# SCH_Esp-Wled-_ready__2024-12-15.net
KiCad netlist of a schematic drawn in EasyEDA
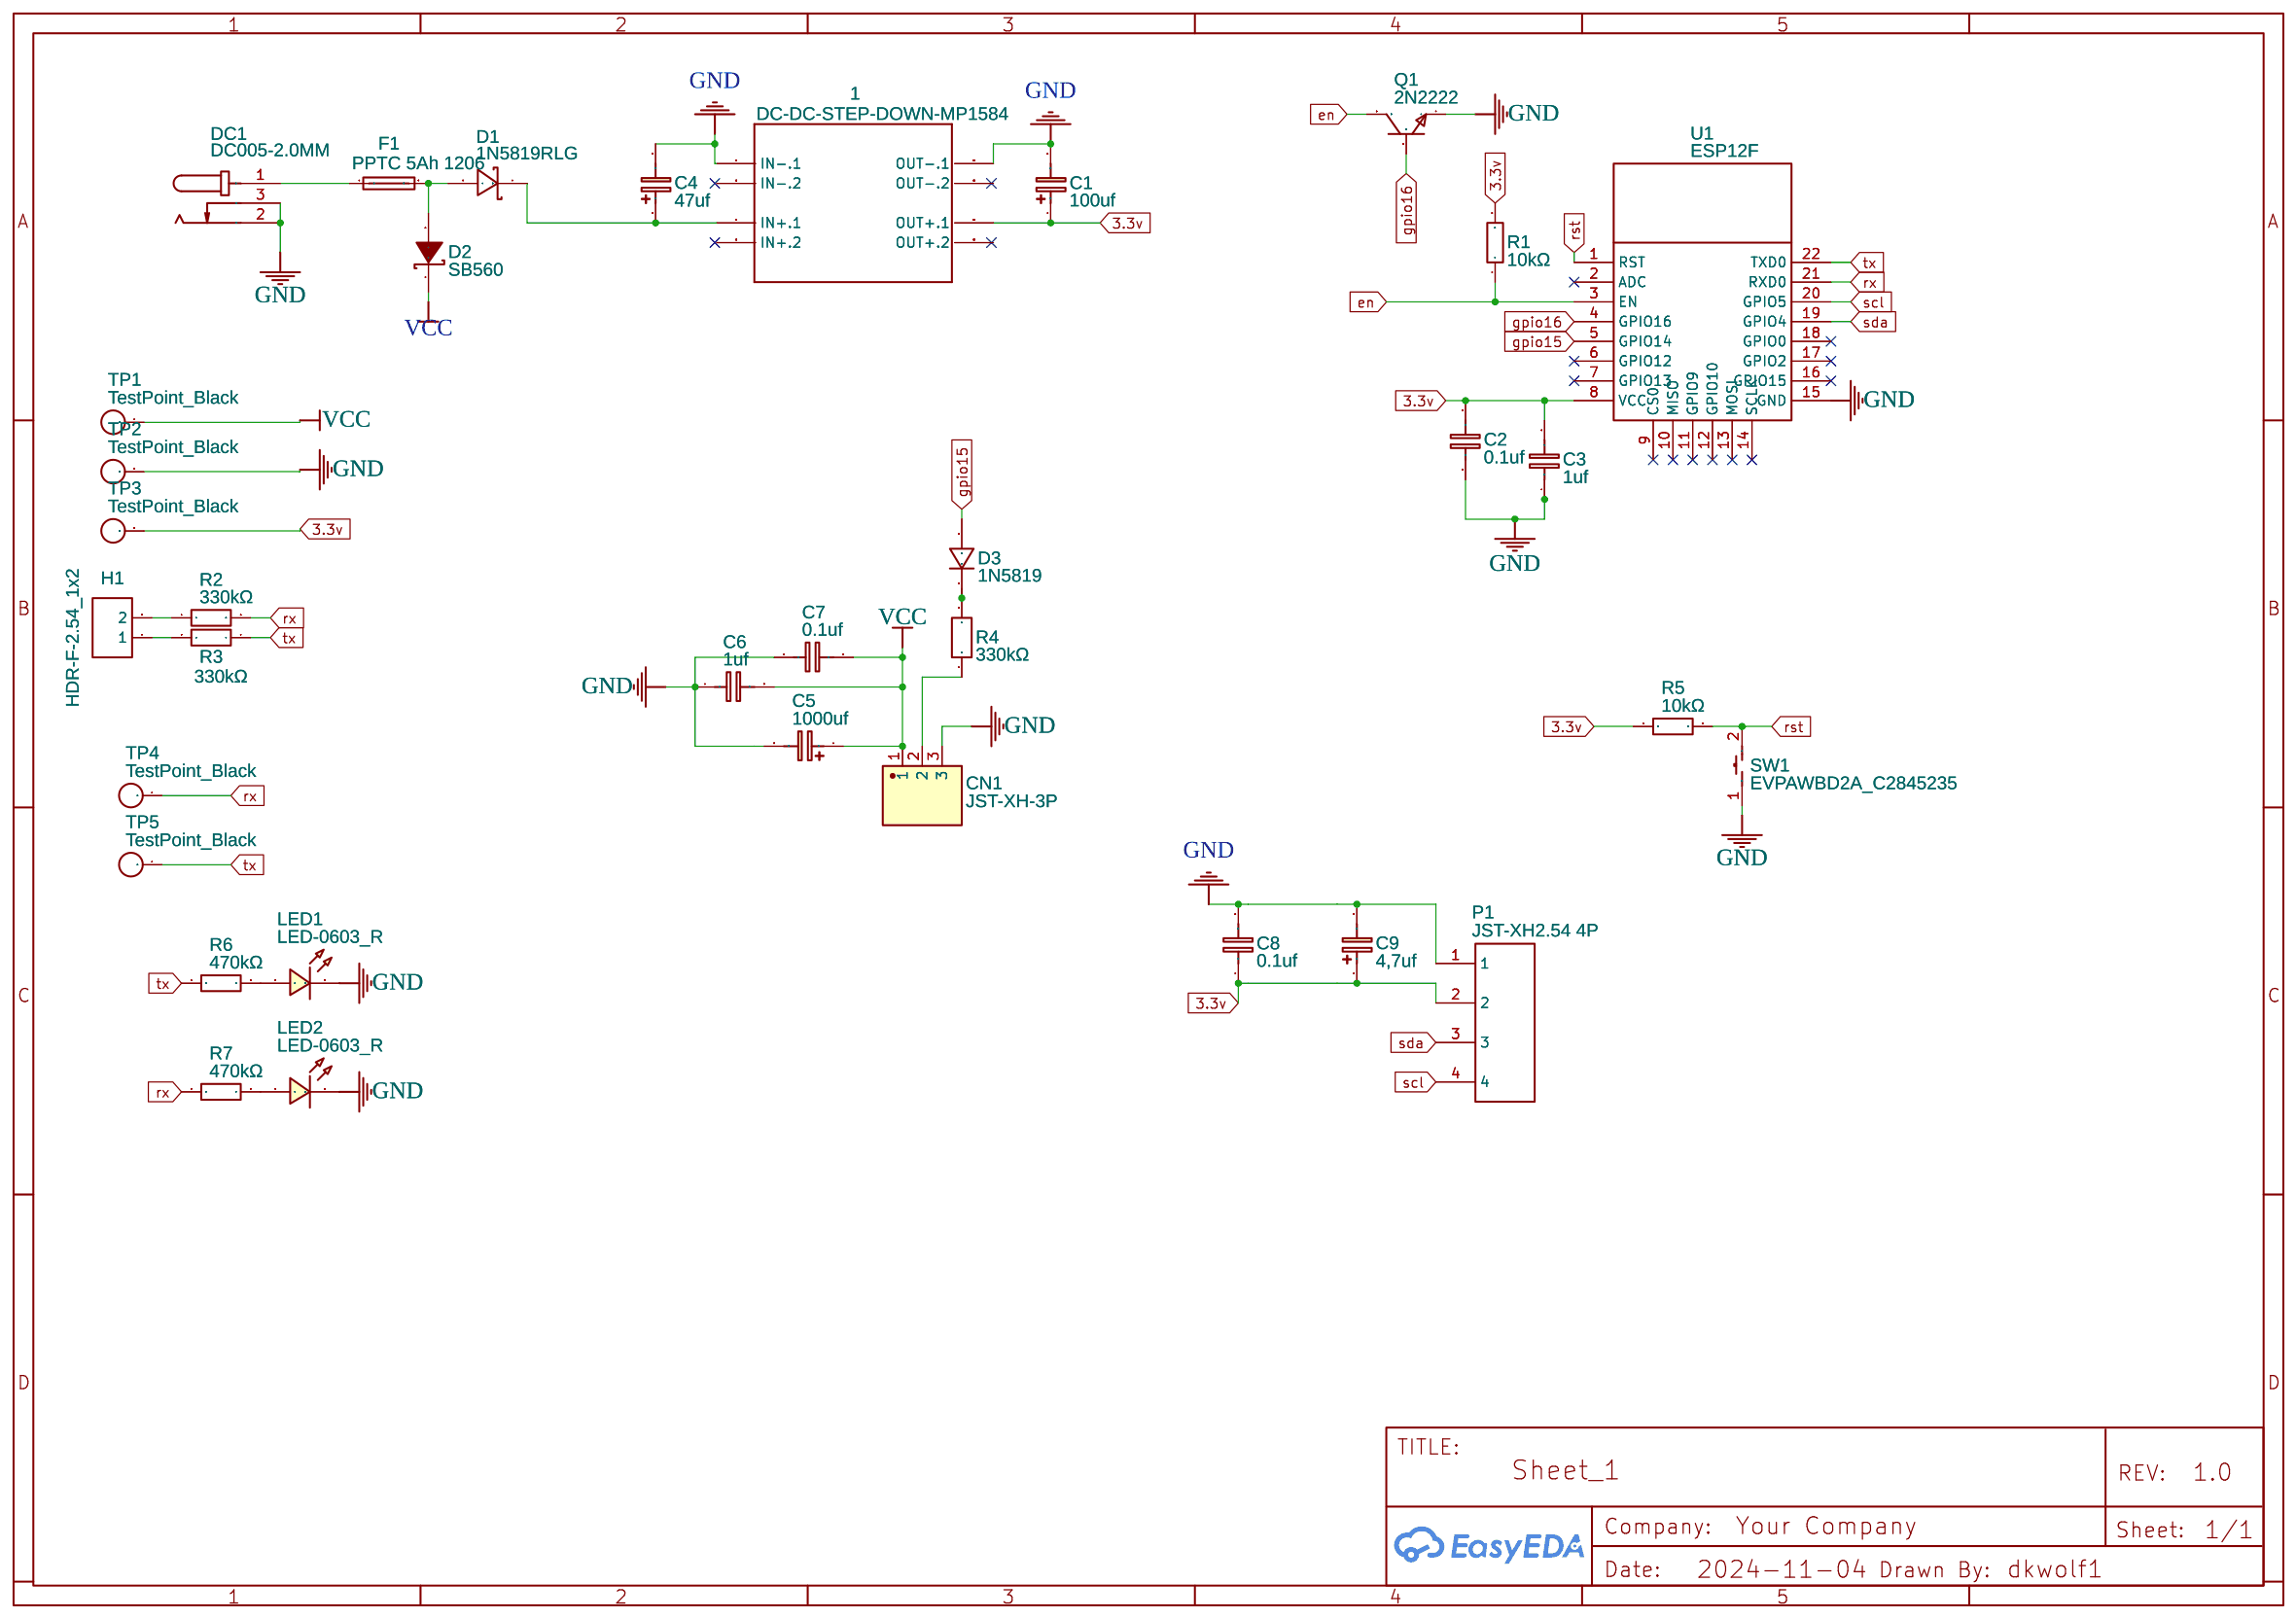
[diagram p0: schematic sheet]

(export (version "E")
  (design (tool "Eeschema 10.0.6"))
  (components
    (comp (ref "1") (value "DC-DC-STEP-DOWN-MP1584") (libsource (lib "") (part "DC-DC-STEP-DOWN-MP1584")))
    (comp (ref "C1") (value "100uf") (libsource (lib "") (part "CE_SMD_D5.0×H5.5_EU_2")))
    (comp (ref "C2") (value "0.1uf") (libsource (lib "") (part "C_0603_EU")))
    (comp (ref "C3") (value "1uf") (libsource (lib "") (part "C_0603_EU")))
    (comp (ref "C4") (value "47uf") (libsource (lib "") (part "CE_SMD_D5.0×H5.5_EU")))
    (comp (ref "C5") (value "1000uf") (libsource (lib "") (part "CE_SMD_D8.0×H10.5_EU")))
    (comp (ref "C6") (value "1uf") (libsource (lib "") (part "C_0603_EU_1")))
    (comp (ref "C7") (value "0.1uf") (libsource (lib "") (part "C_0603_EU_1")))
    (comp (ref "C8") (value "0.1uf") (libsource (lib "") (part "C_0603_EU_2")))
    (comp (ref "C9") (value "4,7uf") (libsource (lib "") (part "CE_SMD_D5.0×H5.5_EU_1")))
    (comp (ref "CN1")
      (value "JST-XH-3P")
      (fields (field (name "Manufacturer Part") "B4B-XH-A(LF)(SN)") (field (name "Manufacturer") "JST"))
      (libsource (lib "") (part "JST-XH-3P"))
    )
    (comp (ref "D1")
      (value "1N5819RLG")
      (fields (field (name "Manufacturer") "onsemi(安森美)"))
      (libsource (lib "") (part "1N5819RLG"))
    )
    (comp (ref "D2")
      (value "SB560")
      (fields (field (name "Manufacturer") "SMC(桑德斯)"))
      (libsource (lib "") (part "SB560"))
    )
    (comp (ref "D3")
      (value "1N5819")
      (fields (field (name "Manufacturer Part") "1N4007") (field (name "Manufacturer") "SEMTECH"))
      (libsource (lib "") (part "1N4007"))
    )
    (comp (ref "DC1")
      (value "DC005-2.0MM")
      (fields (field (name "Manufacturer") "SOFNG"))
      (libsource (lib "") (part "DC005-2.0MM"))
    )
    (comp (ref "F1")
      (value "PPTC 5Ah 1206")
      (fields (field (name "Manufacturer Part") "JK-nSMD050-24") (field (name "Manufacturer") "JK(金科)"))
      (libsource (lib "") (part "JK-NSMD050-24V"))
    )
    (comp (ref "H1") (value "HDR-F-2.54_1x2") (libsource (lib "") (part "HDR-F-2.54_1x2")))
    (comp (ref "LED1")
      (value "LED-0603_R")
      (fields
        (field (name "Manufacturer Part") "19-217/R6C-AL1M2VY/3T")
        (field (name "Manufacturer") "EVERLIGHT(台湾亿光)")
      )
      (libsource (lib "") (part "LED-0603_R"))
    )
    (comp (ref "LED2")
      (value "LED-0603_R")
      (fields
        (field (name "Manufacturer Part") "19-217/R6C-AL1M2VY/3T")
        (field (name "Manufacturer") "EVERLIGHT(台湾亿光)")
      )
      (libsource (lib "") (part "LED-0603_R"))
    )
    (comp (ref "P1") (value "JST-XH2.54 4P") (libsource (lib "") (part "JST-XH2.54 4P")))
    (comp (ref "Q1")
      (value "2N2222")
      (fields (field (name "Manufacturer Part") "2N2222A") (field (name "Manufacturer") "ST(先科)"))
      (libsource (lib "") (part "2N2222"))
    )
    (comp (ref "R1")
      (value "10kΩ")
      (fields (field (name "Manufacturer Part") "RC1206JR-0710KL") (field (name "Manufacturer") "YAGEO(国巨)"))
      (libsource (lib "") (part "RC1206JR-0710KL_1"))
    )
    (comp (ref "R2")
      (value "330kΩ")
      (fields
        (field (name "Manufacturer Part") "1206W4F3303T5E")
        (field (name "Manufacturer") "UNI-ROYAL(厚声)")
      )
      (libsource (lib "") (part "1206W4F3303T5E"))
    )
    (comp (ref "R3")
      (value "330kΩ")
      (fields
        (field (name "Manufacturer Part") "1206W4F3303T5E")
        (field (name "Manufacturer") "UNI-ROYAL(厚声)")
      )
      (libsource (lib "") (part "1206W4F3303T5E_1"))
    )
    (comp (ref "R4")
      (value "330kΩ")
      (fields (field (name "Manufacturer Part") "RC1206JR-7W330KL") (field (name "Manufacturer") "YAGEO(国巨)"))
      (libsource (lib "") (part "RC1206JR-7W330KL"))
    )
    (comp (ref "R5")
      (value "10kΩ")
      (fields (field (name "Manufacturer Part") "RC1206JR-0710KL") (field (name "Manufacturer") "YAGEO(国巨)"))
      (libsource (lib "") (part "RC1206JR-0710KL"))
    )
    (comp (ref "R6")
      (value "470kΩ")
      (fields (field (name "Manufacturer Part") "RC1206FR-07470KL") (field (name "Manufacturer") "YAGEO(国巨)"))
      (libsource (lib "") (part "RC1206FR-07470KL"))
    )
    (comp (ref "R7")
      (value "470kΩ")
      (fields (field (name "Manufacturer Part") "RC1206FR-07470KL") (field (name "Manufacturer") "YAGEO(国巨)"))
      (libsource (lib "") (part "RC1206FR-07470KL"))
    )
    (comp (ref "SW1")
      (value "EVPAWBD2A_C2845235")
      (fields (field (name "Manufacturer Part") "EVPAWBD2A") (field (name "Manufacturer") "PANASONIC(松下)"))
      (libsource (lib "") (part "EVPAWBD2A_C2845235"))
    )
    (comp (ref "TP1") (value "TestPoint_Black") (libsource (lib "") (part "TEST_TESTPOINT")))
    (comp (ref "TP2") (value "TestPoint_Black") (libsource (lib "") (part "TEST_TESTPOINT")))
    (comp (ref "TP3") (value "TestPoint_Black") (libsource (lib "") (part "TEST_TESTPOINT")))
    (comp (ref "TP4") (value "TestPoint_Black") (libsource (lib "") (part "TEST_TESTPOINT")))
    (comp (ref "TP5") (value "TestPoint_Black") (libsource (lib "") (part "TEST_TESTPOINT")))
    (comp (ref "U1") (value "ESP12F") (libsource (lib "") (part "ESP12F")))
  )
  (nets
    (net (code "1") (name "3.3v") (class "Default")
      (node (ref "1") (pin "OUT+.1") (pinfunction "OUT+.1_OUT+.1") (pintype "unspecified"))
      (node (ref "C1") (pin "1") (pinfunction "1_1") (pintype "unspecified"))
      (node (ref "C2") (pin "2") (pinfunction "2_2") (pintype "unspecified"))
      (node (ref "C3") (pin "2") (pinfunction "2_2") (pintype "unspecified"))
      (node (ref "C8") (pin "1") (pinfunction "1_1") (pintype "unspecified"))
      (node (ref "C9") (pin "1") (pinfunction "1_1") (pintype "unspecified"))
      (node (ref "P1") (pin "2") (pinfunction "2_2") (pintype "unspecified"))
      (node (ref "R1") (pin "2") (pinfunction "2_2") (pintype "input"))
      (node (ref "R5") (pin "1") (pinfunction "1_1") (pintype "input"))
      (node (ref "TP3") (pin "1") (pinfunction "2_1") (pintype "unspecified"))
      (node (ref "U1") (pin "8") (pinfunction "VCC_8") (pintype "unspecified"))
    )
    (net (code "2") (name "GND") (class "Default")
      (node (ref "1") (pin "IN-.1") (pinfunction "IN-.1_IN-.1") (pintype "unspecified"))
      (node (ref "1") (pin "OUT-.1") (pinfunction "OUT-.1_OUT-.1") (pintype "unspecified"))
      (node (ref "C1") (pin "2") (pinfunction "2_2") (pintype "unspecified"))
      (node (ref "C2") (pin "1") (pinfunction "1_1") (pintype "unspecified"))
      (node (ref "C3") (pin "1") (pinfunction "1_1") (pintype "unspecified"))
      (node (ref "C4") (pin "2") (pinfunction "2_2") (pintype "unspecified"))
      (node (ref "C5") (pin "2") (pinfunction "2_2") (pintype "unspecified"))
      (node (ref "C6") (pin "1") (pinfunction "1_1") (pintype "unspecified"))
      (node (ref "C7") (pin "1") (pinfunction "1_1") (pintype "unspecified"))
      (node (ref "C8") (pin "2") (pinfunction "2_2") (pintype "unspecified"))
      (node (ref "C9") (pin "2") (pinfunction "2_2") (pintype "unspecified"))
      (node (ref "CN1") (pin "3") (pinfunction "3_3") (pintype "unspecified"))
      (node (ref "DC1") (pin "2") (pinfunction "2_2") (pintype "unspecified"))
      (node (ref "DC1") (pin "3") (pinfunction "3_3") (pintype "unspecified"))
      (node (ref "LED1") (pin "2") (pinfunction "2_2") (pintype "unspecified"))
      (node (ref "LED2") (pin "2") (pinfunction "2_2") (pintype "unspecified"))
      (node (ref "P1") (pin "1") (pinfunction "1_1") (pintype "unspecified"))
      (node (ref "Q1") (pin "1") (pinfunction "E_1") (pintype "unspecified"))
      (node (ref "SW1") (pin "1") (pinfunction "1_1") (pintype "unspecified"))
      (node (ref "TP2") (pin "1") (pinfunction "2_1") (pintype "unspecified"))
      (node (ref "U1") (pin "15") (pinfunction "GND_15") (pintype "unspecified"))
    )
    (net (code "3") (name "Net-(CN1-Pad2)") (class "Default")
      (node (ref "CN1") (pin "2") (pinfunction "2_2") (pintype "unspecified"))
      (node (ref "R4") (pin "1") (pinfunction "1_1") (pintype "unspecified"))
    )
    (net (code "4") (name "Net-(D1-A)") (class "Default")
      (node (ref "D1") (pin "2") (pinfunction "A_2") (pintype "unspecified"))
      (node (ref "D2") (pin "2") (pinfunction "A_2") (pintype "unspecified"))
      (node (ref "F1") (pin "2") (pinfunction "2_2") (pintype "unspecified"))
    )
    (net (code "5") (name "Net-(D1-C)") (class "Default")
      (node (ref "1") (pin "IN+.1") (pinfunction "IN+.1_IN+.1") (pintype "unspecified"))
      (node (ref "C4") (pin "1") (pinfunction "1_1") (pintype "unspecified"))
      (node (ref "D1") (pin "1") (pinfunction "C_1") (pintype "unspecified"))
    )
    (net (code "6") (name "Net-(D3-Pad1)") (class "Default")
      (node (ref "D3") (pin "1") (pinfunction "1_1") (pintype "unspecified"))
      (node (ref "R4") (pin "2") (pinfunction "2_2") (pintype "unspecified"))
    )
    (net (code "7") (name "Net-(DC1-Pad1)") (class "Default")
      (node (ref "DC1") (pin "1") (pinfunction "1_1") (pintype "unspecified"))
      (node (ref "F1") (pin "1") (pinfunction "1_1") (pintype "unspecified"))
    )
    (net (code "8") (name "Net-(H1-Pad1)") (class "Default")
      (node (ref "H1") (pin "1") (pinfunction "1_1") (pintype "input"))
      (node (ref "R3") (pin "2") (pinfunction "2_2") (pintype "input"))
    )
    (net (code "9") (name "Net-(H1-Pad2)") (class "Default")
      (node (ref "H1") (pin "2") (pinfunction "2_2") (pintype "input"))
      (node (ref "R2") (pin "1") (pinfunction "1_1") (pintype "input"))
    )
    (net (code "10") (name "Net-(LED1-Pad1)") (class "Default")
      (node (ref "LED1") (pin "1") (pinfunction "1_1") (pintype "unspecified"))
      (node (ref "R6") (pin "2") (pinfunction "2_2") (pintype "input"))
    )
    (net (code "11") (name "Net-(LED2-Pad1)") (class "Default")
      (node (ref "LED2") (pin "1") (pinfunction "1_1") (pintype "unspecified"))
      (node (ref "R7") (pin "2") (pinfunction "2_2") (pintype "input"))
    )
    (net (code "12") (name "VCC") (class "Default")
      (node (ref "C5") (pin "1") (pinfunction "1_1") (pintype "unspecified"))
      (node (ref "C6") (pin "2") (pinfunction "2_2") (pintype "unspecified"))
      (node (ref "C7") (pin "2") (pinfunction "2_2") (pintype "unspecified"))
      (node (ref "CN1") (pin "1") (pinfunction "1_1") (pintype "unspecified"))
      (node (ref "D2") (pin "1") (pinfunction "K_1") (pintype "unspecified"))
      (node (ref "TP1") (pin "1") (pinfunction "2_1") (pintype "unspecified"))
    )
    (net (code "13") (name "en") (class "Default")
      (node (ref "Q1") (pin "3") (pinfunction "C_3") (pintype "unspecified"))
      (node (ref "R1") (pin "1") (pinfunction "1_1") (pintype "input"))
      (node (ref "U1") (pin "3") (pinfunction "EN_3") (pintype "unspecified"))
    )
    (net (code "14") (name "gpio15") (class "Default")
      (node (ref "D3") (pin "2") (pinfunction "2_2") (pintype "unspecified"))
      (node (ref "U1") (pin "5") (pinfunction "GPIO14_5") (pintype "unspecified"))
    )
    (net (code "15") (name "gpio16") (class "Default")
      (node (ref "Q1") (pin "2") (pinfunction "B_2") (pintype "unspecified"))
      (node (ref "U1") (pin "4") (pinfunction "GPIO16_4") (pintype "unspecified"))
    )
    (net (code "16") (name "rst") (class "Default")
      (node (ref "R5") (pin "2") (pinfunction "2_2") (pintype "input"))
      (node (ref "SW1") (pin "2") (pinfunction "2_2") (pintype "unspecified"))
      (node (ref "U1") (pin "1") (pinfunction "RST_1") (pintype "unspecified"))
    )
    (net (code "17") (name "rx") (class "Default")
      (node (ref "R2") (pin "2") (pinfunction "2_2") (pintype "input"))
      (node (ref "R7") (pin "1") (pinfunction "1_1") (pintype "input"))
      (node (ref "TP4") (pin "1") (pinfunction "2_1") (pintype "unspecified"))
      (node (ref "U1") (pin "21") (pinfunction "RXD0_21") (pintype "unspecified"))
    )
    (net (code "18") (name "scl") (class "Default")
      (node (ref "P1") (pin "4") (pinfunction "4_4") (pintype "unspecified"))
      (node (ref "U1") (pin "20") (pinfunction "GPIO5_20") (pintype "unspecified"))
    )
    (net (code "19") (name "sda") (class "Default")
      (node (ref "P1") (pin "3") (pinfunction "3_3") (pintype "unspecified"))
      (node (ref "U1") (pin "19") (pinfunction "GPIO4_19") (pintype "unspecified"))
    )
    (net (code "20") (name "tx") (class "Default")
      (node (ref "R3") (pin "1") (pinfunction "1_1") (pintype "input"))
      (node (ref "R6") (pin "1") (pinfunction "1_1") (pintype "input"))
      (node (ref "TP5") (pin "1") (pinfunction "2_1") (pintype "unspecified"))
      (node (ref "U1") (pin "22") (pinfunction "TXD0_22") (pintype "unspecified"))
    )
    (net (code "21") (name "unconnected-(1-PadIN+.2)") (class "Default")
      (node (ref "1") (pin "IN+.2") (pinfunction "IN+.2_IN+.2") (pintype "unspecified"))
    )
    (net (code "22") (name "unconnected-(1-PadIN-.2)") (class "Default")
      (node (ref "1") (pin "IN-.2") (pinfunction "IN-.2_IN-.2") (pintype "unspecified"))
    )
    (net (code "23") (name "unconnected-(1-PadOUT+.2)") (class "Default")
      (node (ref "1") (pin "OUT+.2") (pinfunction "OUT+.2_OUT+.2") (pintype "unspecified"))
    )
    (net (code "24") (name "unconnected-(1-PadOUT-.2)") (class "Default")
      (node (ref "1") (pin "OUT-.2") (pinfunction "OUT-.2_OUT-.2") (pintype "unspecified"))
    )
    (net (code "25") (name "unconnected-(U1-ADC-Pad2)") (class "Default")
      (node (ref "U1") (pin "2") (pinfunction "ADC_2") (pintype "unspecified+no_connect"))
    )
    (net (code "26") (name "unconnected-(U1-CS0-Pad9)") (class "Default")
      (node (ref "U1") (pin "9") (pinfunction "CS0_9") (pintype "unspecified+no_connect"))
    )
    (net (code "27") (name "unconnected-(U1-GPIO0-Pad18)") (class "Default")
      (node (ref "U1") (pin "18") (pinfunction "GPIO0_18") (pintype "unspecified+no_connect"))
    )
    (net (code "28") (name "unconnected-(U1-GPIO2-Pad17)") (class "Default")
      (node (ref "U1") (pin "17") (pinfunction "GPIO2_17") (pintype "unspecified+no_connect"))
    )
    (net (code "29") (name "unconnected-(U1-GPIO9-Pad11)") (class "Default")
      (node (ref "U1") (pin "11") (pinfunction "GPIO9_11") (pintype "unspecified+no_connect"))
    )
    (net (code "30") (name "unconnected-(U1-GPIO10-Pad12)") (class "Default")
      (node (ref "U1") (pin "12") (pinfunction "GPIO10_12") (pintype "unspecified+no_connect"))
    )
    (net (code "31") (name "unconnected-(U1-GPIO12-Pad6)") (class "Default")
      (node (ref "U1") (pin "6") (pinfunction "GPIO12_6") (pintype "unspecified+no_connect"))
    )
    (net (code "32") (name "unconnected-(U1-GPIO13-Pad7)") (class "Default")
      (node (ref "U1") (pin "7") (pinfunction "GPIO13_7") (pintype "unspecified+no_connect"))
    )
    (net (code "33") (name "unconnected-(U1-GPIO15-Pad16)") (class "Default")
      (node (ref "U1") (pin "16") (pinfunction "GPIO15_16") (pintype "unspecified+no_connect"))
    )
    (net (code "34") (name "unconnected-(U1-MISO-Pad10)") (class "Default")
      (node (ref "U1") (pin "10") (pinfunction "MISO_10") (pintype "unspecified+no_connect"))
    )
    (net (code "35") (name "unconnected-(U1-MOSI-Pad13)") (class "Default")
      (node (ref "U1") (pin "13") (pinfunction "MOSI_13") (pintype "unspecified+no_connect"))
    )
    (net (code "36") (name "unconnected-(U1-SCLK-Pad14)") (class "Default")
      (node (ref "U1") (pin "14") (pinfunction "SCLK_14") (pintype "unspecified+no_connect"))
    )
  )
)
